# debug.net
KiCad netlist of a schematic drawn in Altium Designer
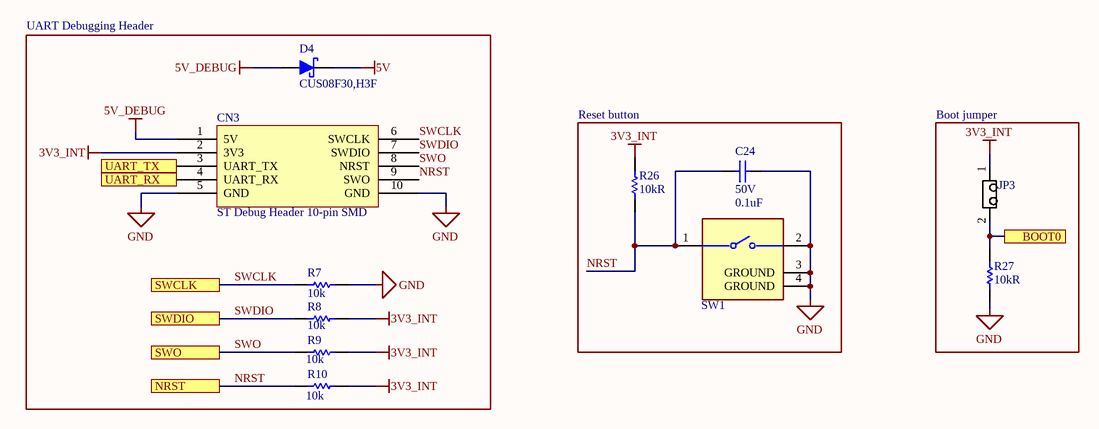
[diagram p0: debug.SchDoc]

(export (version "E")
  (design (tool "Eeschema 10.0.6"))
  (components
    (comp (ref "C24")
      (value "CL10B104JB8NNNC")
      (footprint "FP-CL10-0_1-MFG")
      (description "CAP CER 0.1UF 50V X7R 0603")
      (fields
        (field (name "TOLERANCE") "5%")
        (field (name "VOLTAGE") "50V")
        (field (name "CAPACITANCE") "0.1uF")
      )
      (libsource (lib "AUVIC") (part "CAP-NP-2"))
    )
    (comp (ref "CN3")
      (value "ST Debug Header 10-pin SMD")
      (footprint "ST Debug Header 10-pin SMD-Footprint-1")
      (description "CONN HEADER SMD 10POS 2.54MM")
      (libsource (lib "AUVIC") (part "ST Debug Header 10-pin"))
    )
    (comp (ref "D4")
      (value "CUS08F30,H3F")
      (footprint "SC-76")
      (description "Diode Schottky 30V 800mA Surface Mount USC")
      (libsource (lib "") (part "Symbol_1"))
    )
    (comp (ref "JP3")
      (value "1x2 Male Header")
      (footprint "2X1 Males Header")
      (fields (field (name "MADE BY") "Andy Bates"))
      (libsource (lib "AUVIC") (part "1x2 Male Header"))
    )
    (comp (ref "R7")
      (value "10k")
      (footprint "RESC1608N(0603\")")
      (description "10kR, 1%, 1/10W, 0603 SMD")
      (fields (field (name "MADE BY") "Ashwin Sira"))
      (libsource (lib "AUVIC") (part "Symbol"))
    )
    (comp (ref "R8")
      (value "10k")
      (footprint "RESC1608N(0603\")")
      (description "10kR, 1%, 1/10W, 0603 SMD")
      (fields (field (name "MADE BY") "Ashwin Sira"))
      (libsource (lib "AUVIC") (part "Symbol"))
    )
    (comp (ref "R9")
      (value "10k")
      (footprint "RESC1608N(0603\")")
      (description "10kR, 1%, 1/10W, 0603 SMD")
      (fields (field (name "MADE BY") "Ashwin Sira"))
      (libsource (lib "AUVIC") (part "Symbol"))
    )
    (comp (ref "R10")
      (value "10k")
      (footprint "RESC1608N(0603\")")
      (description "10kR, 1%, 1/10W, 0603 SMD")
      (fields (field (name "MADE BY") "Ashwin Sira"))
      (libsource (lib "AUVIC") (part "Symbol"))
    )
    (comp (ref "R26")
      (value "10kR")
      (footprint "RESC1608N(0603\")")
      (description "10kR, 1%, 1/10W, 0603 SMD")
      (fields (field (name "MADE BY") "Ashwin Sira"))
      (libsource (lib "AUVIC") (part "Symbol"))
    )
    (comp (ref "R27")
      (value "10kR")
      (footprint "RESC1608N(0603\")")
      (description "10kR, 1%, 1/10W, 0603 SMD")
      (fields (field (name "MADE BY") "Ashwin Sira"))
      (libsource (lib "AUVIC") (part "Symbol"))
    )
    (comp (ref "SW1")
      (value "PTS636SKG25SMTRLFS")
      (footprint "FP-PTS636_SKG25_SMTR_LFS-MFG")
      (description "PTS636 Series SPST-NO Off-Mom 250 gf Top Actuated Gull Wing SMT Tactile Switch")
      (libsource (lib "AUVIC") (part "bdfe703aeb3461bf7c331fe9d798369"))
    )
  )
  (nets
    (net (code "1") (name "/BOOT0") (class "Default")
      (node (ref "JP3") (pin "2") (pinfunction "2_2") (pintype "passive"))
      (node (ref "R27") (pin "1") (pinfunction "1_1") (pintype "passive"))
    )
    (net (code "2") (name "/NRST") (class "Default")
      (node (ref "C24") (pin "2") (pinfunction "2_2") (pintype "passive"))
      (node (ref "CN3") (pin "9") (pinfunction "SWO_9") (pintype "passive"))
      (node (ref "R10") (pin "1") (pinfunction "1_1") (pintype "passive"))
      (node (ref "R26") (pin "2") (pinfunction "2_2") (pintype "passive"))
      (node (ref "SW1") (pin "1") (pinfunction "1_1") (pintype "passive"))
    )
    (net (code "3") (name "/SWCLK") (class "Default")
      (node (ref "CN3") (pin "6") (pinfunction "SWCLK_6") (pintype "passive"))
      (node (ref "R7") (pin "1") (pinfunction "1_1") (pintype "passive"))
    )
    (net (code "4") (name "/SWDIO") (class "Default")
      (node (ref "CN3") (pin "7") (pinfunction "SWDIO_7") (pintype "passive"))
      (node (ref "R8") (pin "1") (pinfunction "1_1") (pintype "passive"))
    )
    (net (code "5") (name "/SWO") (class "Default")
      (node (ref "CN3") (pin "8") (pinfunction "NRST_8") (pintype "passive"))
      (node (ref "R9") (pin "1") (pinfunction "1_1") (pintype "passive"))
    )
    (net (code "6") (name "/UART_RX") (class "Default")
      (node (ref "CN3") (pin "4") (pinfunction "UART_RX_4") (pintype "passive"))
    )
    (net (code "7") (name "/UART_TX") (class "Default")
      (node (ref "CN3") (pin "3") (pinfunction "UART_TX_3") (pintype "passive"))
    )
    (net (code "8") (name "3V3_INT") (class "Default")
      (node (ref "CN3") (pin "2") (pinfunction "3V3_2") (pintype "passive"))
      (node (ref "JP3") (pin "1") (pinfunction "1_1") (pintype "passive"))
      (node (ref "R10") (pin "2") (pinfunction "2_2") (pintype "passive"))
      (node (ref "R26") (pin "1") (pinfunction "1_1") (pintype "passive"))
      (node (ref "R8") (pin "2") (pinfunction "2_2") (pintype "passive"))
      (node (ref "R9") (pin "2") (pinfunction "2_2") (pintype "passive"))
    )
    (net (code "9") (name "5V") (class "Default")
      (node (ref "D4") (pin "K") (pinfunction "Cathode_K") (pintype "passive"))
    )
    (net (code "10") (name "5V_DEBUG") (class "Default")
      (node (ref "CN3") (pin "1") (pinfunction "5V_1") (pintype "passive"))
      (node (ref "D4") (pin "A") (pinfunction "Anode_A") (pintype "passive"))
    )
    (net (code "11") (name "GND") (class "Default")
      (node (ref "C24") (pin "1") (pinfunction "1_1") (pintype "passive"))
      (node (ref "CN3") (pin "10") (pinfunction "GND_10") (pintype "passive"))
      (node (ref "CN3") (pin "5") (pinfunction "GND_5") (pintype "passive"))
      (node (ref "R27") (pin "2") (pinfunction "2_2") (pintype "passive"))
      (node (ref "R7") (pin "2") (pinfunction "2_2") (pintype "passive"))
      (node (ref "SW1") (pin "2") (pinfunction "2_2") (pintype "passive"))
      (node (ref "SW1") (pin "3") (pinfunction "GROUND_3") (pintype "power_in"))
      (node (ref "SW1") (pin "4") (pinfunction "GROUND_4") (pintype "power_in"))
    )
  )
)
